# Sheet1.net
KiCad netlist of a schematic drawn in Altium Designer
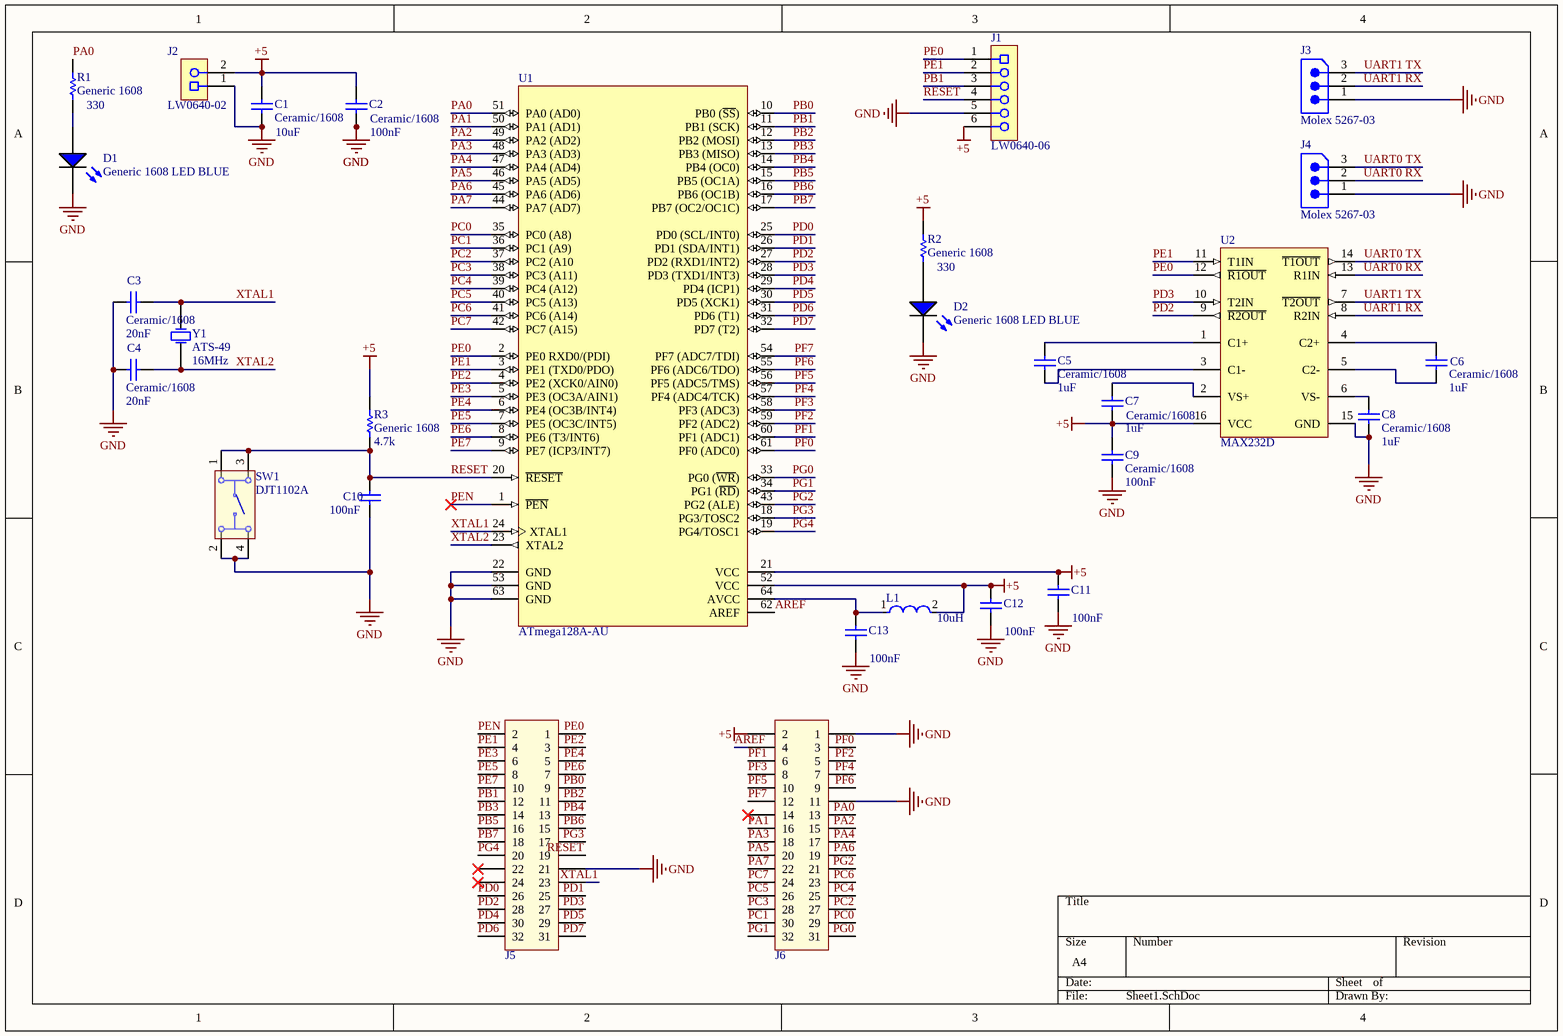
[diagram p0: Sheet1.SchDoc]

(export (version "E")
  (design (tool "Eeschema 10.0.6"))
  (components
    (comp (ref "C1")
      (value "Ceramic/1608")
      (footprint "Generic 1608-Footprint-1")
      (description "Generic 1608 Ceramic Capacitor")
      (fields (field (name "ALTIUM_VALUE") "10uF"))
      (libsource (lib "C6H6`s Vault") (part "Generic 1608"))
    )
    (comp (ref "C2")
      (value "Ceramic/1608")
      (footprint "Generic 1608-Footprint-1")
      (description "Generic 1608 Ceramic Capacitor")
      (fields (field (name "ALTIUM_VALUE") "100nF"))
      (libsource (lib "C6H6`s Vault") (part "Generic 1608"))
    )
    (comp (ref "C3")
      (value "Ceramic/1608")
      (footprint "Generic 1608-Footprint-1")
      (description "Generic 1608 Ceramic Capacitor")
      (fields (field (name "ALTIUM_VALUE") "20nF"))
      (libsource (lib "C6H6`s Vault") (part "Generic 1608"))
    )
    (comp (ref "C4")
      (value "Ceramic/1608")
      (footprint "Generic 1608-Footprint-1")
      (description "Generic 1608 Ceramic Capacitor")
      (fields (field (name "ALTIUM_VALUE") "20nF"))
      (libsource (lib "C6H6`s Vault") (part "Generic 1608"))
    )
    (comp (ref "C5")
      (value "Ceramic/1608")
      (footprint "Generic 1608-Footprint-1")
      (description "Generic 1608 Ceramic Capacitor")
      (fields (field (name "ALTIUM_VALUE") "1uF"))
      (libsource (lib "C6H6`s Vault") (part "Generic 1608"))
    )
    (comp (ref "C6")
      (value "Ceramic/1608")
      (footprint "Generic 1608-Footprint-1")
      (description "Generic 1608 Ceramic Capacitor")
      (fields (field (name "ALTIUM_VALUE") "1uF"))
      (libsource (lib "C6H6`s Vault") (part "Generic 1608"))
    )
    (comp (ref "C7")
      (value "Ceramic/1608")
      (footprint "Generic 1608-Footprint-1")
      (description "Generic 1608 Ceramic Capacitor")
      (fields (field (name "ALTIUM_VALUE") "1uF"))
      (libsource (lib "C6H6`s Vault") (part "Generic 1608"))
    )
    (comp (ref "C8")
      (value "Ceramic/1608")
      (footprint "Generic 1608-Footprint-1")
      (description "Generic 1608 Ceramic Capacitor")
      (fields (field (name "ALTIUM_VALUE") "1uF"))
      (libsource (lib "C6H6`s Vault") (part "Generic 1608"))
    )
    (comp (ref "C9")
      (value "Ceramic/1608")
      (footprint "Generic 1608-Footprint-1")
      (description "Generic 1608 Ceramic Capacitor")
      (fields (field (name "ALTIUM_VALUE") "100nF"))
      (libsource (lib "C6H6`s Vault") (part "Generic 1608"))
    )
    (comp (ref "C10")
      (value "100nF")
      (footprint "Generic 1608-Footprint-1")
      (description "Generic 1608 Ceramic Capacitor")
      (fields (field (name "Comment") "Ceramic/1608"))
      (libsource (lib "C6H6`s Vault") (part "Generic 1608"))
    )
    (comp (ref "C11")
      (value "100nF")
      (footprint "Generic 1608-Footprint-1")
      (description "Generic 1608 Ceramic Capacitor")
      (fields (field (name "Comment") "Ceramic/1608"))
      (libsource (lib "C6H6`s Vault") (part "Generic 1608"))
    )
    (comp (ref "C12")
      (value "100nF")
      (footprint "Generic 1608-Footprint-1")
      (description "Generic 1608 Ceramic Capacitor")
      (fields (field (name "Comment") "Ceramic/1608"))
      (libsource (lib "C6H6`s Vault") (part "Generic 1608"))
    )
    (comp (ref "C13")
      (value "100nF")
      (footprint "Generic 1608-Footprint-1")
      (description "Generic 1608 Ceramic Capacitor")
      (fields (field (name "Comment") "Ceramic/1608"))
      (libsource (lib "C6H6`s Vault") (part "Generic 1608"))
    )
    (comp (ref "D1")
      (value "Generic 1608 LED BLUE")
      (footprint "Generic 1608 LED BLUE-Footprint-1")
      (description "Generic 1608 LED <BLUE>")
      (libsource (lib "C6H6`s Vault") (part "1608/BLUE"))
    )
    (comp (ref "D2")
      (value "Generic 1608 LED BLUE")
      (footprint "Generic 1608 LED BLUE-Footprint-1")
      (description "Generic 1608 LED <BLUE>")
      (libsource (lib "C6H6`s Vault") (part "1608/BLUE"))
    )
    (comp (ref "J1")
      (value "LW0640-06")
      (footprint "LW0640-06")
      (description "6-pin Molex 5045 compatible Hanlim Connector")
      (libsource (lib "C6H6`s Vault") (part "LW0640-06"))
    )
    (comp (ref "J2")
      (value "LW0640-02")
      (footprint "LW0640-02")
      (description "2-pin Molex 5045 compatible Hanlim Connector")
      (libsource (lib "C6H6`s Vault") (part "LW0640-02"))
    )
    (comp (ref "J3")
      (value "Molex 5267-03")
      (footprint "Molex 5267-03-Footprint")
      (description "2.50mm (.098\") Pitch SPOX Wire-to-Board Header, Vertical, Shrouded, 3 Circuits, Tin (Sn) Plating")
      (libsource (lib "C6H6`s Vault") (part "22-03-5035"))
    )
    (comp (ref "J4")
      (value "Molex 5267-03")
      (footprint "Molex 5267-03-Footprint")
      (description "2.50mm (.098\") Pitch SPOX Wire-to-Board Header, Vertical, Shrouded, 3 Circuits, Tin (Sn) Plating")
      (libsource (lib "C6H6`s Vault") (part "22-03-5035"))
    )
    (comp (ref "J5")
      (value "61303221121")
      (footprint "61303221121")
      (description "Pin Header WR-PHD, pitch 2.54 mm, THT, Vertical, dual row, 32 pin")
      (fields (field (name "PUBLISHER") "Wurth Elektronik"))
      (libsource (lib "C6H6`s Vault") (part "61303221121"))
    )
    (comp (ref "J6")
      (value "61303221121")
      (footprint "61303221121")
      (description "Pin Header WR-PHD, pitch 2.54 mm, THT, Vertical, dual row, 32 pin")
      (fields (field (name "PUBLISHER") "Wurth Elektronik"))
      (libsource (lib "C6H6`s Vault") (part "61303221121"))
    )
    (comp (ref "L1")
      (value "10uH")
      (footprint "FP-MLZ1608-MFG")
      (description "FIXED IND 10UH 250MA 1.05 OHM")
      (fields (field (name "MANUFACTURER") "TDK") (field (name "TOLERANCE") "20%"))
      (libsource (lib "Altium Content Vault") (part "725321dda6339637d4d059423bc1c3c"))
    )
    (comp (ref "R1")
      (value "Generic 1608")
      (footprint "Generic 1608-Footprint-1")
      (description "Generic 1608 Resistor")
      (fields (field (name "ALTIUM_VALUE") "330"))
      (libsource (lib "") (part "Generic 1608_1"))
    )
    (comp (ref "R2")
      (value "Generic 1608")
      (footprint "Generic 1608-Footprint-1")
      (description "Generic 1608 Resistor")
      (fields (field (name "ALTIUM_VALUE") "330"))
      (libsource (lib "") (part "Generic 1608_1"))
    )
    (comp (ref "R3")
      (value "Generic 1608")
      (footprint "Generic 1608-Footprint-1")
      (description "Generic 1608 Resistor")
      (fields (field (name "ALTIUM_VALUE") "4.7k"))
      (libsource (lib "") (part "Generic 1608_1"))
    )
    (comp (ref "SW1")
      (value "DJT1102A")
      (footprint "DJT1102A-Footprint-1")
      (description "6.0mm 6.0mm tact switch")
      (libsource (lib "C6H6`s Vault") (part "DJT1102A"))
    )
    (comp (ref "U1")
      (value "ATmega128A-AU")
      (footprint "64A_N")
      (libsource (lib "Altium Content Vault") (part "MC-8B-ATM64A-SQ64"))
    )
    (comp (ref "U2")
      (value "MAX232D")
      (footprint "D0016A_M")
      (description "Dual EIA-232 Driver / Receiver, 0 to 70 degC, 16-Pin SOIC (D), Green (RoHS & no Sb/Br)")
      (libsource (lib "Altium Content Vault") (part "TI-MAX232-SOIC_D-16"))
    )
    (comp (ref "Y1")
      (value "ATS-49")
      (footprint "ATS-49-Footprint-1")
      (description "Crystal ATS-49U")
      (fields (field (name "ALTIUM_VALUE") "16MHz"))
      (libsource (lib "C6H6`s Vault") (part "ATS-49"))
    )
  )
  (nets
    (net (code "1") (name "+5") (class "Default")
      (node (ref "C1") (pin "1") (pinfunction "1_1") (pintype "passive"))
      (node (ref "C11") (pin "1") (pinfunction "1_1") (pintype "passive"))
      (node (ref "C12") (pin "1") (pinfunction "1_1") (pintype "passive"))
      (node (ref "C2") (pin "1") (pinfunction "1_1") (pintype "passive"))
      (node (ref "C7") (pin "1") (pinfunction "1_1") (pintype "passive"))
      (node (ref "C9") (pin "2") (pinfunction "2_2") (pintype "passive"))
      (node (ref "J1") (pin "6") (pinfunction "6_6") (pintype "passive"))
      (node (ref "J2") (pin "2") (pinfunction "2_2") (pintype "passive"))
      (node (ref "J6") (pin "2") (pinfunction "2_2") (pintype "passive"))
      (node (ref "L1") (pin "2") (pinfunction "2_2") (pintype "passive"))
      (node (ref "R2") (pin "2") (pinfunction "2_2") (pintype "passive"))
      (node (ref "R3") (pin "2") (pinfunction "2_2") (pintype "passive"))
      (node (ref "U1") (pin "21") (pinfunction "VCC_21") (pintype "power_in"))
      (node (ref "U1") (pin "52") (pinfunction "VCC_52") (pintype "power_in"))
      (node (ref "U2") (pin "16") (pinfunction "VCC_16") (pintype "power_in"))
    )
    (net (code "2") (name "/AREF") (class "Default")
      (node (ref "J6") (pin "4") (pinfunction "4_4") (pintype "passive"))
      (node (ref "U1") (pin "62") (pinfunction "AREF_62") (pintype "power_in"))
    )
    (net (code "3") (name "/PA0") (class "Default")
      (node (ref "J6") (pin "13") (pinfunction "13_13") (pintype "passive"))
      (node (ref "R1") (pin "2") (pinfunction "2_2") (pintype "passive"))
      (node (ref "U1") (pin "51") (pinfunction "PA0_(AD0)_51") (pintype "bidirectional"))
    )
    (net (code "4") (name "/PA1") (class "Default")
      (node (ref "J6") (pin "16") (pinfunction "16_16") (pintype "passive"))
      (node (ref "U1") (pin "50") (pinfunction "PA1_(AD1)_50") (pintype "bidirectional"))
    )
    (net (code "5") (name "/PA2") (class "Default")
      (node (ref "J6") (pin "15") (pinfunction "15_15") (pintype "passive"))
      (node (ref "U1") (pin "49") (pinfunction "PA2_(AD2)_49") (pintype "bidirectional"))
    )
    (net (code "6") (name "/PA3") (class "Default")
      (node (ref "J6") (pin "18") (pinfunction "18_18") (pintype "passive"))
      (node (ref "U1") (pin "48") (pinfunction "PA3_(AD3)_48") (pintype "bidirectional"))
    )
    (net (code "7") (name "/PA4") (class "Default")
      (node (ref "J6") (pin "17") (pinfunction "17_17") (pintype "passive"))
      (node (ref "U1") (pin "47") (pinfunction "PA4_(AD4)_47") (pintype "bidirectional"))
    )
    (net (code "8") (name "/PA5") (class "Default")
      (node (ref "J6") (pin "20") (pinfunction "20_20") (pintype "passive"))
      (node (ref "U1") (pin "46") (pinfunction "PA5_(AD5)_46") (pintype "bidirectional"))
    )
    (net (code "9") (name "/PA6") (class "Default")
      (node (ref "J6") (pin "19") (pinfunction "19_19") (pintype "passive"))
      (node (ref "U1") (pin "45") (pinfunction "PA6_(AD6)_45") (pintype "bidirectional"))
    )
    (net (code "10") (name "/PA7") (class "Default")
      (node (ref "J6") (pin "22") (pinfunction "22_22") (pintype "passive"))
      (node (ref "U1") (pin "44") (pinfunction "PA7_(AD7)_44") (pintype "bidirectional"))
    )
    (net (code "11") (name "/PB0") (class "Default")
      (node (ref "J5") (pin "9") (pinfunction "9_9") (pintype "passive"))
      (node (ref "U1") (pin "10") (pinfunction "PB0_(~{SS})_10") (pintype "bidirectional"))
    )
    (net (code "12") (name "/PB1") (class "Default")
      (node (ref "J1") (pin "3") (pinfunction "3_3") (pintype "passive"))
      (node (ref "J5") (pin "12") (pinfunction "12_12") (pintype "passive"))
      (node (ref "U1") (pin "11") (pinfunction "PB1_(SCK)_11") (pintype "bidirectional"))
    )
    (net (code "13") (name "/PB2") (class "Default")
      (node (ref "J5") (pin "11") (pinfunction "11_11") (pintype "passive"))
      (node (ref "U1") (pin "12") (pinfunction "PB2_(MOSI)_12") (pintype "bidirectional"))
    )
    (net (code "14") (name "/PB3") (class "Default")
      (node (ref "J5") (pin "14") (pinfunction "14_14") (pintype "passive"))
      (node (ref "U1") (pin "13") (pinfunction "PB3_(MISO)_13") (pintype "bidirectional"))
    )
    (net (code "15") (name "/PB4") (class "Default")
      (node (ref "J5") (pin "13") (pinfunction "13_13") (pintype "passive"))
      (node (ref "U1") (pin "14") (pinfunction "PB4_(OC0)_14") (pintype "bidirectional"))
    )
    (net (code "16") (name "/PB5") (class "Default")
      (node (ref "J5") (pin "16") (pinfunction "16_16") (pintype "passive"))
      (node (ref "U1") (pin "15") (pinfunction "PB5_(OC1A)_15") (pintype "bidirectional"))
    )
    (net (code "17") (name "/PB6") (class "Default")
      (node (ref "J5") (pin "15") (pinfunction "15_15") (pintype "passive"))
      (node (ref "U1") (pin "16") (pinfunction "PB6_(OC1B)_16") (pintype "bidirectional"))
    )
    (net (code "18") (name "/PB7") (class "Default")
      (node (ref "J5") (pin "18") (pinfunction "18_18") (pintype "passive"))
      (node (ref "U1") (pin "17") (pinfunction "PB7_(OC2/OC1C)_17") (pintype "bidirectional"))
    )
    (net (code "19") (name "/PC0") (class "Default")
      (node (ref "J6") (pin "29") (pinfunction "29_29") (pintype "passive"))
      (node (ref "U1") (pin "35") (pinfunction "PC0_(A8)_35") (pintype "bidirectional"))
    )
    (net (code "20") (name "/PC1") (class "Default")
      (node (ref "J6") (pin "30") (pinfunction "30_30") (pintype "passive"))
      (node (ref "U1") (pin "36") (pinfunction "PC1_(A9)_36") (pintype "bidirectional"))
    )
    (net (code "21") (name "/PC2") (class "Default")
      (node (ref "J6") (pin "27") (pinfunction "27_27") (pintype "passive"))
      (node (ref "U1") (pin "37") (pinfunction "PC2_(A10_37") (pintype "bidirectional"))
    )
    (net (code "22") (name "/PC3") (class "Default")
      (node (ref "J6") (pin "28") (pinfunction "28_28") (pintype "passive"))
      (node (ref "U1") (pin "38") (pinfunction "PC3_(A11)_38") (pintype "bidirectional"))
    )
    (net (code "23") (name "/PC4") (class "Default")
      (node (ref "J6") (pin "25") (pinfunction "25_25") (pintype "passive"))
      (node (ref "U1") (pin "39") (pinfunction "PC4_(A12)_39") (pintype "bidirectional"))
    )
    (net (code "24") (name "/PC5") (class "Default")
      (node (ref "J6") (pin "26") (pinfunction "26_26") (pintype "passive"))
      (node (ref "U1") (pin "40") (pinfunction "PC5_(A13)_40") (pintype "bidirectional"))
    )
    (net (code "25") (name "/PC6") (class "Default")
      (node (ref "J6") (pin "23") (pinfunction "23_23") (pintype "passive"))
      (node (ref "U1") (pin "41") (pinfunction "PC6_(A14)_41") (pintype "bidirectional"))
    )
    (net (code "26") (name "/PC7") (class "Default")
      (node (ref "J6") (pin "24") (pinfunction "24_24") (pintype "passive"))
      (node (ref "U1") (pin "42") (pinfunction "PC7_(A15)_42") (pintype "bidirectional"))
    )
    (net (code "27") (name "/PD0") (class "Default")
      (node (ref "J5") (pin "26") (pinfunction "26_26") (pintype "passive"))
      (node (ref "U1") (pin "25") (pinfunction "PD0_(SCL/INT0)_25") (pintype "bidirectional"))
    )
    (net (code "28") (name "/PD1") (class "Default")
      (node (ref "J5") (pin "25") (pinfunction "25_25") (pintype "passive"))
      (node (ref "U1") (pin "26") (pinfunction "PD1_(SDA/INT1)_26") (pintype "bidirectional"))
    )
    (net (code "29") (name "/PD2") (class "Default")
      (node (ref "J5") (pin "28") (pinfunction "28_28") (pintype "passive"))
      (node (ref "U1") (pin "27") (pinfunction "PD2_(RXD1/INT2)_27") (pintype "bidirectional"))
      (node (ref "U2") (pin "9") (pinfunction "~{R2OUT}_9") (pintype "output"))
    )
    (net (code "30") (name "/PD3") (class "Default")
      (node (ref "J5") (pin "27") (pinfunction "27_27") (pintype "passive"))
      (node (ref "U1") (pin "28") (pinfunction "PD3_(TXD1/INT3)_28") (pintype "bidirectional"))
      (node (ref "U2") (pin "10") (pinfunction "T2IN_10") (pintype "input"))
    )
    (net (code "31") (name "/PD4") (class "Default")
      (node (ref "J5") (pin "30") (pinfunction "30_30") (pintype "passive"))
      (node (ref "U1") (pin "29") (pinfunction "PD4_(ICP1)_29") (pintype "bidirectional"))
    )
    (net (code "32") (name "/PD5") (class "Default")
      (node (ref "J5") (pin "29") (pinfunction "29_29") (pintype "passive"))
      (node (ref "U1") (pin "30") (pinfunction "PD5_(XCK1)_30") (pintype "bidirectional"))
    )
    (net (code "33") (name "/PD6") (class "Default")
      (node (ref "J5") (pin "32") (pinfunction "32_32") (pintype "passive"))
      (node (ref "U1") (pin "31") (pinfunction "PD6_(T1)_31") (pintype "bidirectional"))
    )
    (net (code "34") (name "/PD7") (class "Default")
      (node (ref "J5") (pin "31") (pinfunction "31_31") (pintype "passive"))
      (node (ref "U1") (pin "32") (pinfunction "PD7_(T2)_32") (pintype "bidirectional"))
    )
    (net (code "35") (name "/PE0") (class "Default")
      (node (ref "J1") (pin "1") (pinfunction "1_1") (pintype "passive"))
      (node (ref "J5") (pin "1") (pinfunction "1_1") (pintype "passive"))
      (node (ref "U1") (pin "2") (pinfunction "PE0_RXD0/(PDI)_2") (pintype "bidirectional"))
      (node (ref "U2") (pin "12") (pinfunction "~{R1OUT}_12") (pintype "output"))
    )
    (net (code "36") (name "/PE1") (class "Default")
      (node (ref "J1") (pin "2") (pinfunction "2_2") (pintype "passive"))
      (node (ref "J5") (pin "4") (pinfunction "4_4") (pintype "passive"))
      (node (ref "U1") (pin "3") (pinfunction "PE1_(TXD0/PDO)_3") (pintype "bidirectional"))
      (node (ref "U2") (pin "11") (pinfunction "T1IN_11") (pintype "input"))
    )
    (net (code "37") (name "/PE2") (class "Default")
      (node (ref "J5") (pin "3") (pinfunction "3_3") (pintype "passive"))
      (node (ref "U1") (pin "4") (pinfunction "PE2_(XCK0/AIN0)_4") (pintype "bidirectional"))
    )
    (net (code "38") (name "/PE3") (class "Default")
      (node (ref "J5") (pin "6") (pinfunction "6_6") (pintype "passive"))
      (node (ref "U1") (pin "5") (pinfunction "PE3_(OC3A/AIN1)_5") (pintype "bidirectional"))
    )
    (net (code "39") (name "/PE4") (class "Default")
      (node (ref "J5") (pin "5") (pinfunction "5_5") (pintype "passive"))
      (node (ref "U1") (pin "6") (pinfunction "PE4_(OC3B/INT4)_6") (pintype "bidirectional"))
    )
    (net (code "40") (name "/PE5") (class "Default")
      (node (ref "J5") (pin "8") (pinfunction "8_8") (pintype "passive"))
      (node (ref "U1") (pin "7") (pinfunction "PE5_(OC3C/INT5)_7") (pintype "bidirectional"))
    )
    (net (code "41") (name "/PE6") (class "Default")
      (node (ref "J5") (pin "7") (pinfunction "7_7") (pintype "passive"))
      (node (ref "U1") (pin "8") (pinfunction "PE6_(T3/INT6)_8") (pintype "bidirectional"))
    )
    (net (code "42") (name "/PE7") (class "Default")
      (node (ref "J5") (pin "10") (pinfunction "10_10") (pintype "passive"))
      (node (ref "U1") (pin "9") (pinfunction "PE7_(ICP3/INT7)_9") (pintype "bidirectional"))
    )
    (net (code "43") (name "/PEN") (class "Default")
      (node (ref "J5") (pin "2") (pinfunction "2_2") (pintype "passive"))
      (node (ref "U1") (pin "1") (pinfunction "~{PEN}_1") (pintype "input"))
    )
    (net (code "44") (name "/PF0") (class "Default")
      (node (ref "J6") (pin "3") (pinfunction "3_3") (pintype "passive"))
      (node (ref "U1") (pin "61") (pinfunction "PF0_(ADC0)_61") (pintype "bidirectional"))
    )
    (net (code "45") (name "/PF1") (class "Default")
      (node (ref "J6") (pin "6") (pinfunction "6_6") (pintype "passive"))
      (node (ref "U1") (pin "60") (pinfunction "PF1_(ADC1)_60") (pintype "bidirectional"))
    )
    (net (code "46") (name "/PF2") (class "Default")
      (node (ref "J6") (pin "5") (pinfunction "5_5") (pintype "passive"))
      (node (ref "U1") (pin "59") (pinfunction "PF2_(ADC2)_59") (pintype "bidirectional"))
    )
    (net (code "47") (name "/PF3") (class "Default")
      (node (ref "J6") (pin "8") (pinfunction "8_8") (pintype "passive"))
      (node (ref "U1") (pin "58") (pinfunction "PF3_(ADC3)_58") (pintype "bidirectional"))
    )
    (net (code "48") (name "/PF4") (class "Default")
      (node (ref "J6") (pin "7") (pinfunction "7_7") (pintype "passive"))
      (node (ref "U1") (pin "57") (pinfunction "PF4_(ADC4/TCK)_57") (pintype "bidirectional"))
    )
    (net (code "49") (name "/PF5") (class "Default")
      (node (ref "J6") (pin "10") (pinfunction "10_10") (pintype "passive"))
      (node (ref "U1") (pin "56") (pinfunction "PF5_(ADC5/TMS)_56") (pintype "bidirectional"))
    )
    (net (code "50") (name "/PF6") (class "Default")
      (node (ref "J6") (pin "9") (pinfunction "9_9") (pintype "passive"))
      (node (ref "U1") (pin "55") (pinfunction "PF6_(ADC6/TDO)_55") (pintype "bidirectional"))
    )
    (net (code "51") (name "/PF7") (class "Default")
      (node (ref "J6") (pin "12") (pinfunction "12_12") (pintype "passive"))
      (node (ref "U1") (pin "54") (pinfunction "PF7_(ADC7/TDI)_54") (pintype "bidirectional"))
    )
    (net (code "52") (name "/PG0") (class "Default")
      (node (ref "J6") (pin "31") (pinfunction "31_31") (pintype "passive"))
      (node (ref "U1") (pin "33") (pinfunction "PG0_(~{WR})_33") (pintype "bidirectional"))
    )
    (net (code "53") (name "/PG1") (class "Default")
      (node (ref "J6") (pin "32") (pinfunction "32_32") (pintype "passive"))
      (node (ref "U1") (pin "34") (pinfunction "PG1_(~{RD})_34") (pintype "bidirectional"))
    )
    (net (code "54") (name "/PG2") (class "Default")
      (node (ref "J6") (pin "21") (pinfunction "21_21") (pintype "passive"))
      (node (ref "U1") (pin "43") (pinfunction "PG2_(ALE)_43") (pintype "bidirectional"))
    )
    (net (code "55") (name "/PG3") (class "Default")
      (node (ref "J5") (pin "17") (pinfunction "17_17") (pintype "passive"))
      (node (ref "U1") (pin "18") (pinfunction "PG3/TOSC2_18") (pintype "bidirectional"))
    )
    (net (code "56") (name "/PG4") (class "Default")
      (node (ref "J5") (pin "20") (pinfunction "20_20") (pintype "passive"))
      (node (ref "U1") (pin "19") (pinfunction "PG4/TOSC1_19") (pintype "bidirectional"))
    )
    (net (code "57") (name "/RESET") (class "Default")
      (node (ref "C10") (pin "1") (pinfunction "1_1") (pintype "passive"))
      (node (ref "J1") (pin "4") (pinfunction "4_4") (pintype "passive"))
      (node (ref "J5") (pin "19") (pinfunction "19_19") (pintype "passive"))
      (node (ref "R3") (pin "1") (pinfunction "1_1") (pintype "passive"))
      (node (ref "SW1") (pin "1") (pinfunction "1_1") (pintype "passive"))
      (node (ref "SW1") (pin "3") (pinfunction "3_3") (pintype "passive"))
      (node (ref "U1") (pin "20") (pinfunction "~{RESET}_20") (pintype "input"))
    )
    (net (code "58") (name "/UART0 RX") (class "Default")
      (node (ref "J4") (pin "2") (pinfunction "2_2") (pintype "passive"))
      (node (ref "U2") (pin "13") (pinfunction "R1IN_13") (pintype "input"))
    )
    (net (code "59") (name "/UART0 TX") (class "Default")
      (node (ref "J4") (pin "3") (pinfunction "3_3") (pintype "passive"))
      (node (ref "U2") (pin "14") (pinfunction "~{T1OUT}_14") (pintype "output"))
    )
    (net (code "60") (name "/UART1 RX") (class "Default")
      (node (ref "J3") (pin "2") (pinfunction "2_2") (pintype "passive"))
      (node (ref "U2") (pin "8") (pinfunction "R2IN_8") (pintype "input"))
    )
    (net (code "61") (name "/UART1 TX") (class "Default")
      (node (ref "J3") (pin "3") (pinfunction "3_3") (pintype "passive"))
      (node (ref "U2") (pin "7") (pinfunction "~{T2OUT}_7") (pintype "output"))
    )
    (net (code "62") (name "/XTAL1") (class "Default")
      (node (ref "C3") (pin "2") (pinfunction "2_2") (pintype "passive"))
      (node (ref "J5") (pin "23") (pinfunction "23_23") (pintype "passive"))
      (node (ref "U1") (pin "24") (pinfunction "XTAL1_24") (pintype "input"))
      (node (ref "Y1") (pin "2") (pinfunction "OSC2_2") (pintype "passive"))
    )
    (net (code "63") (name "/XTAL2") (class "Default")
      (node (ref "C4") (pin "2") (pinfunction "2_2") (pintype "passive"))
      (node (ref "U1") (pin "23") (pinfunction "XTAL2_23") (pintype "output"))
      (node (ref "Y1") (pin "1") (pinfunction "OSC1_1") (pintype "passive"))
    )
    (net (code "64") (name "GND") (class "Default")
      (node (ref "C1") (pin "2") (pinfunction "2_2") (pintype "passive"))
      (node (ref "C10") (pin "2") (pinfunction "2_2") (pintype "passive"))
      (node (ref "C11") (pin "2") (pinfunction "2_2") (pintype "passive"))
      (node (ref "C12") (pin "2") (pinfunction "2_2") (pintype "passive"))
      (node (ref "C13") (pin "2") (pinfunction "2_2") (pintype "passive"))
      (node (ref "C2") (pin "2") (pinfunction "2_2") (pintype "passive"))
      (node (ref "C3") (pin "1") (pinfunction "1_1") (pintype "passive"))
      (node (ref "C4") (pin "1") (pinfunction "1_1") (pintype "passive"))
      (node (ref "C8") (pin "1") (pinfunction "1_1") (pintype "passive"))
      (node (ref "C9") (pin "1") (pinfunction "1_1") (pintype "passive"))
      (node (ref "D1") (pin "2") (pinfunction "K_2") (pintype "passive"))
      (node (ref "D2") (pin "2") (pinfunction "K_2") (pintype "passive"))
      (node (ref "J1") (pin "5") (pinfunction "5_5") (pintype "passive"))
      (node (ref "J2") (pin "1") (pinfunction "1_1") (pintype "passive"))
      (node (ref "J3") (pin "1") (pinfunction "1_1") (pintype "passive"))
      (node (ref "J4") (pin "1") (pinfunction "1_1") (pintype "passive"))
      (node (ref "J5") (pin "21") (pinfunction "21_21") (pintype "passive"))
      (node (ref "J6") (pin "1") (pinfunction "1_1") (pintype "passive"))
      (node (ref "J6") (pin "11") (pinfunction "11_11") (pintype "passive"))
      (node (ref "SW1") (pin "2") (pinfunction "2_2") (pintype "passive"))
      (node (ref "SW1") (pin "4") (pinfunction "4_4") (pintype "passive"))
      (node (ref "U1") (pin "22") (pinfunction "GND_22") (pintype "power_in"))
      (node (ref "U1") (pin "53") (pinfunction "GND_53") (pintype "power_in"))
      (node (ref "U1") (pin "63") (pinfunction "GND_63") (pintype "power_in"))
      (node (ref "U2") (pin "15") (pinfunction "GND_15") (pintype "power_in"))
    )
    (net (code "65") (name "Net-(D1-A)") (class "Default")
      (node (ref "D1") (pin "1") (pinfunction "A_1") (pintype "passive"))
      (node (ref "R1") (pin "1") (pinfunction "1_1") (pintype "passive"))
    )
    (net (code "66") (name "Net-(D2-A)") (class "Default")
      (node (ref "D2") (pin "1") (pinfunction "A_1") (pintype "passive"))
      (node (ref "R2") (pin "1") (pinfunction "1_1") (pintype "passive"))
    )
    (net (code "67") (name "Net-(U1-AVCC)") (class "Default")
      (node (ref "C13") (pin "1") (pinfunction "1_1") (pintype "passive"))
      (node (ref "L1") (pin "1") (pinfunction "1_1") (pintype "passive"))
      (node (ref "U1") (pin "64") (pinfunction "AVCC_64") (pintype "power_in"))
    )
    (net (code "68") (name "Net-(U2-C1+)") (class "Default")
      (node (ref "C5") (pin "2") (pinfunction "2_2") (pintype "passive"))
      (node (ref "U2") (pin "1") (pinfunction "C1+_1") (pintype "passive"))
    )
    (net (code "69") (name "Net-(U2-C1-)") (class "Default")
      (node (ref "C5") (pin "1") (pinfunction "1_1") (pintype "passive"))
      (node (ref "U2") (pin "3") (pinfunction "C1-_3") (pintype "passive"))
    )
    (net (code "70") (name "Net-(U2-C2+)") (class "Default")
      (node (ref "C6") (pin "2") (pinfunction "2_2") (pintype "passive"))
      (node (ref "U2") (pin "4") (pinfunction "C2+_4") (pintype "passive"))
    )
    (net (code "71") (name "Net-(U2-C2-)") (class "Default")
      (node (ref "C6") (pin "1") (pinfunction "1_1") (pintype "passive"))
      (node (ref "U2") (pin "5") (pinfunction "C2-_5") (pintype "passive"))
    )
    (net (code "72") (name "Net-(U2-VS+)") (class "Default")
      (node (ref "C7") (pin "2") (pinfunction "2_2") (pintype "passive"))
      (node (ref "U2") (pin "2") (pinfunction "VS+_2") (pintype "power_in"))
    )
    (net (code "73") (name "Net-(U2-VS-)") (class "Default")
      (node (ref "C8") (pin "2") (pinfunction "2_2") (pintype "passive"))
      (node (ref "U2") (pin "6") (pinfunction "VS-_6") (pintype "power_in"))
    )
    (net (code "74") (name "unconnected-(J5-Pad22)") (class "Default")
      (node (ref "J5") (pin "22") (pinfunction "22_22") (pintype "passive+no_connect"))
    )
    (net (code "75") (name "unconnected-(J5-Pad24)") (class "Default")
      (node (ref "J5") (pin "24") (pinfunction "24_24") (pintype "passive+no_connect"))
    )
    (net (code "76") (name "unconnected-(J6-Pad14)") (class "Default")
      (node (ref "J6") (pin "14") (pinfunction "14_14") (pintype "passive+no_connect"))
    )
  )
)
